# CON_EEM.net
KiCad netlist of a schematic drawn in Altium Designer
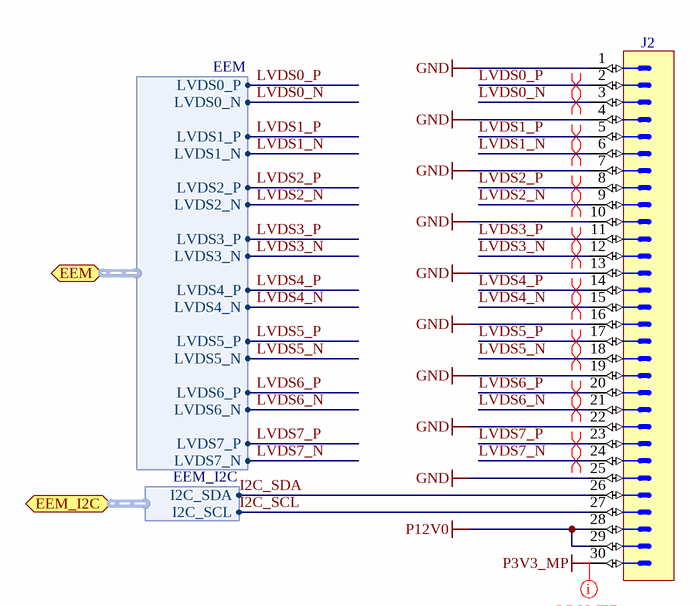
[diagram p0: CON_EEM.SchDoc]

(export (version "E")
  (design (tool "Eeschema 10.0.6"))
  (components
    (comp (ref "J2")
      (value "~")
      (footprint "3M_N2530-6002RB")
      (description "Connector 30 Male")
      (fields
        (field (name "PART NUMBER") "3M_N2530-6002RB")
        (field (name "MANUFACTURER") "3M")
        (field (name "AUTHOR") "CERN DEM JLC")
      )
      (libsource (lib "Connectors") (part "Connector 30 Male"))
    )
  )
  (nets
    (net (code "3") (name "/I2C_SCL") (class "Default")
      (node (ref "J2") (pin "27") (pinfunction "27_27") (pintype "bidirectional"))
    )
    (net (code "4") (name "/I2C_SDA") (class "Default")
      (node (ref "J2") (pin "26") (pinfunction "26_26") (pintype "bidirectional"))
    )
    (net (code "5") (name "/LVDS0_N") (class "Default")
      (node (ref "J2") (pin "3") (pinfunction "3_3") (pintype "bidirectional"))
    )
    (net (code "6") (name "/LVDS0_P") (class "Default")
      (node (ref "J2") (pin "2") (pinfunction "2_2") (pintype "bidirectional"))
    )
    (net (code "7") (name "/LVDS1_N") (class "Default")
      (node (ref "J2") (pin "6") (pinfunction "6_6") (pintype "bidirectional"))
    )
    (net (code "8") (name "/LVDS1_P") (class "Default")
      (node (ref "J2") (pin "5") (pinfunction "5_5") (pintype "bidirectional"))
    )
    (net (code "9") (name "/LVDS2_N") (class "Default")
      (node (ref "J2") (pin "9") (pinfunction "9_9") (pintype "bidirectional"))
    )
    (net (code "10") (name "/LVDS2_P") (class "Default")
      (node (ref "J2") (pin "8") (pinfunction "8_8") (pintype "bidirectional"))
    )
    (net (code "11") (name "/LVDS3_N") (class "Default")
      (node (ref "J2") (pin "12") (pinfunction "12_12") (pintype "bidirectional"))
    )
    (net (code "12") (name "/LVDS3_P") (class "Default")
      (node (ref "J2") (pin "11") (pinfunction "11_11") (pintype "bidirectional"))
    )
    (net (code "13") (name "/LVDS4_N") (class "Default")
      (node (ref "J2") (pin "15") (pinfunction "15_15") (pintype "bidirectional"))
    )
    (net (code "14") (name "/LVDS4_P") (class "Default")
      (node (ref "J2") (pin "14") (pinfunction "14_14") (pintype "bidirectional"))
    )
    (net (code "15") (name "/LVDS5_N") (class "Default")
      (node (ref "J2") (pin "18") (pinfunction "18_18") (pintype "bidirectional"))
    )
    (net (code "16") (name "/LVDS5_P") (class "Default")
      (node (ref "J2") (pin "17") (pinfunction "17_17") (pintype "bidirectional"))
    )
    (net (code "17") (name "/LVDS6_N") (class "Default")
      (node (ref "J2") (pin "21") (pinfunction "21_21") (pintype "bidirectional"))
    )
    (net (code "18") (name "/LVDS6_P") (class "Default")
      (node (ref "J2") (pin "20") (pinfunction "20_20") (pintype "bidirectional"))
    )
    (net (code "19") (name "/LVDS7_N") (class "Default")
      (node (ref "J2") (pin "24") (pinfunction "24_24") (pintype "bidirectional"))
    )
    (net (code "20") (name "/LVDS7_P") (class "Default")
      (node (ref "J2") (pin "23") (pinfunction "23_23") (pintype "bidirectional"))
    )
    (net (code "23") (name "GND") (class "Default")
      (node (ref "J2") (pin "1") (pinfunction "1_1") (pintype "bidirectional"))
      (node (ref "J2") (pin "10") (pinfunction "10_10") (pintype "bidirectional"))
      (node (ref "J2") (pin "13") (pinfunction "13_13") (pintype "bidirectional"))
      (node (ref "J2") (pin "16") (pinfunction "16_16") (pintype "bidirectional"))
      (node (ref "J2") (pin "19") (pinfunction "19_19") (pintype "bidirectional"))
      (node (ref "J2") (pin "22") (pinfunction "22_22") (pintype "bidirectional"))
      (node (ref "J2") (pin "25") (pinfunction "25_25") (pintype "bidirectional"))
      (node (ref "J2") (pin "4") (pinfunction "4_4") (pintype "bidirectional"))
      (node (ref "J2") (pin "7") (pinfunction "7_7") (pintype "bidirectional"))
    )
    (net (code "24") (name "P3V3_MP") (class "Default")
      (node (ref "J2") (pin "30") (pinfunction "30_30") (pintype "bidirectional"))
    )
    (net (code "25") (name "P12V0") (class "Default")
      (node (ref "J2") (pin "28") (pinfunction "28_28") (pintype "bidirectional"))
      (node (ref "J2") (pin "29") (pinfunction "29_29") (pintype "bidirectional"))
    )
  )
)
